# Interface.net
KiCad netlist of a schematic drawn in Altium Designer
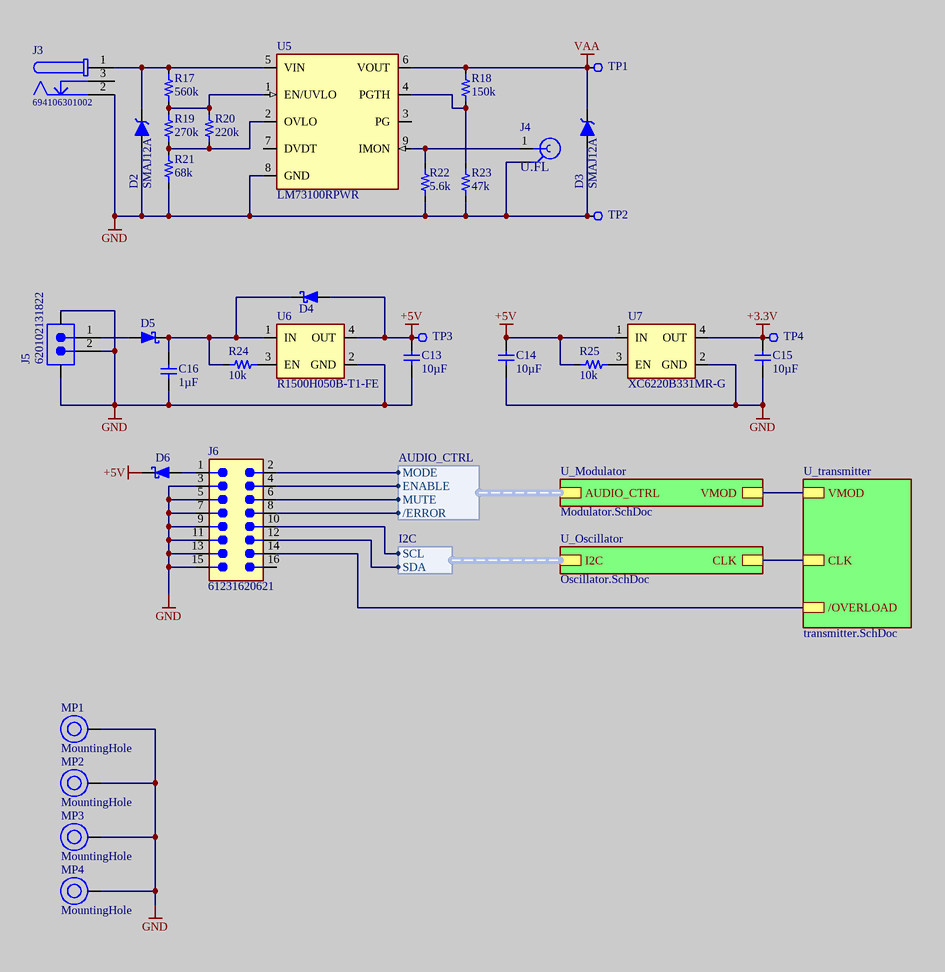
[diagram p0: Interface.SchDoc]

(export (version "E")
  (design (tool "Eeschema 10.0.6"))
  (components
    (comp (ref "C13")
      (value "10µF")
      (footprint "WCAP-CSGP_1210_L3.2W2.5H2")
      (description "WCAP-CSGP Multilayer Ceramic Chip Capacitor, General Purpose, size 1210, X7R, 10µF, 16VDC")
      (fields (field (name "TOLERANCE") "10%") (field (name "JLCPCB PART #") "C319189"))
      (libsource (lib "7c7 Engineering") (part "CAP-NP-2"))
    )
    (comp (ref "C14")
      (value "10µF")
      (footprint "WCAP-CSGP_1210_L3.2W2.5H2")
      (description "WCAP-CSGP Multilayer Ceramic Chip Capacitor, General Purpose, size 1210, X7R, 10µF, 16VDC")
      (fields (field (name "TOLERANCE") "10%") (field (name "JLCPCB PART #") "C319189"))
      (libsource (lib "7c7 Engineering") (part "CAP-NP-2"))
    )
    (comp (ref "C15")
      (value "10µF")
      (footprint "WCAP-CSGP_1210_L3.2W2.5H2")
      (description "WCAP-CSGP Multilayer Ceramic Chip Capacitor, General Purpose, size 1210, X7R, 10µF, 16VDC")
      (fields (field (name "TOLERANCE") "10%") (field (name "JLCPCB PART #") "C319189"))
      (libsource (lib "7c7 Engineering") (part "CAP-NP-2"))
    )
    (comp (ref "C16")
      (value "1µF")
      (footprint "1206-C-N")
      (description "WCAP-CSGP Multilayer Ceramic Chip Capacitor, General Purpose, size 1206, X7R, 1µF, 50VDC")
      (fields (field (name "TOLERANCE") "10%") (field (name "JLCPCB PART #") "C1848"))
      (libsource (lib "7c7 Engineering") (part "CAP-NP-2"))
    )
    (comp (ref "D2")
      (value "SMAJ12A")
      (footprint "DO-214AC_UNI")
      (description "SMAJ Series 19.9 V 0.4 kW Surface Mount Uni-Directional TVS Diode - DO-214AC")
      (fields
        (field (name "MANUFACTURER PART NUMBER") "824500121")
        (field (name "MANUFACTURER") "Wurth Elektronik")
      )
      (libsource (lib "7c7 Engineering") (part "DIODE-ZEN-2"))
    )
    (comp (ref "D3")
      (value "SMAJ12A")
      (footprint "DO-214AC_UNI")
      (description "SMAJ Series 19.9 V 0.4 kW Surface Mount Uni-Directional TVS Diode - DO-214AC")
      (fields
        (field (name "MANUFACTURER PART NUMBER") "824500121")
        (field (name "MANUFACTURER") "Wurth Elektronik")
      )
      (libsource (lib "7c7 Engineering") (part "DIODE-ZEN-2"))
    )
    (comp (ref "D4")
      (value "PMEG10020ELRX")
      (footprint "FP-SOD123W-MFG")
      (description "Diode Schottky 100V 2A 2-Pin SOD-123F T/R")
      (fields (field (name "JLCPCB PART #") "C456130") (field (name "PAGE PART #") "?"))
      (libsource (lib "7c7 Engineering") (part "DIODE-SKY-2"))
    )
    (comp (ref "D5")
      (value "PMEG10020ELRX")
      (footprint "FP-SOD123W-MFG")
      (description "Diode Schottky 100V 2A 2-Pin SOD-123F T/R")
      (fields (field (name "JLCPCB PART #") "C456130") (field (name "PAGE PART #") "?"))
      (libsource (lib "7c7 Engineering") (part "DIODE-SKY-2"))
    )
    (comp (ref "D6")
      (value "PMEG10020ELRX")
      (footprint "FP-SOD123W-MFG")
      (description "Diode Schottky 100V 2A 2-Pin SOD-123F T/R")
      (fields (field (name "JLCPCB PART #") "C456130") (field (name "PAGE PART #") "?"))
      (libsource (lib "7c7 Engineering") (part "DIODE-SKY-2"))
    )
    (comp (ref "J3")
      (value "694106301002")
      (footprint "694106301002")
      (description "WR-DC DC Power Jack Connector, Male, Right Angled, 24V, 5A")
      (fields (field (name "JLCPCB PART #") "C5184829") (field (name "MANUFACTURER") "Wurth Elektronik"))
      (libsource (lib "7c7 Engineering") (part "Symbol"))
    )
    (comp (ref "J4")
      (value "U.FL-R-SMT(10)")
      (footprint "HRS-U.FL-R-SMT_V")
      (fields (field (name "JLCPCB PART #") "C88373") (field (name "MANUFACTURER") "Hirose Electric"))
      (libsource (lib "7c7 Engineering") (part "CN_COAX"))
    )
    (comp (ref "J5")
      (value "620102131822")
      (footprint "620102131822")
      (description "WR-WTB SMT Male Horizontal Shrouded Header, pitch 2mm, 2p")
      (fields
        (field (name "JLCPCB PART #") "C295747")
        (field (name "PAGE PART #") "K620102131822")
        (field (name "PUBLISHER") "Wurth Elektronik")
      )
      (libsource (lib "7c7 Engineering") (part "HDR_2P_2MP"))
    )
    (comp (ref "J6")
      (value "61231620621")
      (footprint "61231620621")
      (description "WR-BHD Male Box Header, SMT Straight, pitch 2.54mm, 2 row, 16 pin")
      (fields (field (name "JLCPCB PART #") "C22387748") (field (name "MANUFACTURER") "Wurth Elektronik"))
      (libsource (lib "7c7 Engineering") (part "CN_M_2x8P"))
    )
    (comp (ref "MP1")
      (value "MountingHole")
      (footprint "PTH-M3D6.5_VIA-RING")
      (libsource (lib "7c7 Engineering") (part "MECH_NO_BOM"))
    )
    (comp (ref "MP2")
      (value "MountingHole")
      (footprint "PTH-M3D6.5_VIA-RING")
      (libsource (lib "7c7 Engineering") (part "MECH_NO_BOM"))
    )
    (comp (ref "MP3")
      (value "MountingHole")
      (footprint "PTH-M3D6.5_VIA-RING")
      (libsource (lib "7c7 Engineering") (part "MECH_NO_BOM"))
    )
    (comp (ref "MP4")
      (value "MountingHole")
      (footprint "PTH-M3D6.5_VIA-RING")
      (libsource (lib "7c7 Engineering") (part "MECH_NO_BOM"))
    )
    (comp (ref "R17")
      (value "560k")
      (footprint "0603-R-N")
      (description "Res Thick Film 0603 560K Ohm 1% 0.1W ±100ppm/°C Molded SMD Punched Carrier T/R")
      (fields (field (name "JLCPCB PART #") "C25822") (field (name "TOLERANCE") "1%"))
      (libsource (lib "7c7 Engineering") (part "RES"))
    )
    (comp (ref "R18")
      (value "150k")
      (footprint "0603-R-N")
      (description "Chip Resistor, Thick Film, General Purpose, 0603, 100mW, 50V, 150 kOhm, +/-1%")
      (fields (field (name "FLIR PART #") "YRES150K-1") (field (name "JLCPCB PART #") "C22807"))
      (libsource (lib "7c7 Engineering") (part "RES"))
    )
    (comp (ref "R19")
      (value "270k")
      (footprint "0603-R-N")
      (description "SMD Chip Resistor, 270 kOhm, ï¿½ 1%, 100 mW, 0603 [1608 Metric], Thick Film, General Purpose")
      (fields (field (name "JLCPCB PART #") "C22965") (field (name "TOLERANCE") "1%"))
      (libsource (lib "7c7 Engineering") (part "RES"))
    )
    (comp (ref "R20")
      (value "220k")
      (footprint "0603-R-N")
      (description "Res Thick Film 0603 220K Ohm 1% 0.1W(1/10W) ±100ppm/C Pad SMD T/R")
      (fields (field (name "TOLERANCE") "1%") (field (name "FLIR PART #") "YRES220K-1"))
      (libsource (lib "7c7 Engineering") (part "RES"))
    )
    (comp (ref "R21")
      (value "68k")
      (footprint "0603-R-N")
      (description "Chip Resistor, Thick Film, General Purpose, 0603, 100mW, 50V, 68 kOhm, +/-1%")
      (fields (field (name "TOLERANCE") "1%") (field (name "JLCPCB PART #") "C114633"))
      (libsource (lib "7c7 Engineering") (part "RES"))
    )
    (comp (ref "R22")
      (value "5.6k")
      (footprint "0603-R-N")
      (description "Res Thick Film 0603 5.6K Ohm 1% 0.1W(1/10W) ±100ppm/C Pad SMD T/R")
      (fields (field (name "JLCPCB PART #") "C23189") (field (name "TOLERANCE") "1%"))
      (libsource (lib "7c7 Engineering") (part "RES"))
    )
    (comp (ref "R23")
      (value "47k")
      (footprint "0603-R-N")
      (description "Chip Resistor, Thick Film, General Purpose, 0603, 100mW, 50V, 47 kOhm, +/-1%")
      (fields (field (name "JLCPCB PART #") "C25819") (field (name "TOLERANCE") "1%"))
      (libsource (lib "7c7 Engineering") (part "RES"))
    )
    (comp (ref "R24")
      (value "10k")
      (footprint "0603-R-N")
      (description "Chip Resistor, Thick Film, General Purpose, 0603, 100mW, 50V, 10 kOhm, +/-1%")
      (fields (field (name "TOLERANCE") "1%") (field (name "JLCPCB PART #") "C25804"))
      (libsource (lib "7c7 Engineering") (part "RES"))
    )
    (comp (ref "R25")
      (value "10k")
      (footprint "0603-R-N")
      (description "Chip Resistor, Thick Film, General Purpose, 0603, 100mW, 50V, 10 kOhm, +/-1%")
      (fields (field (name "TOLERANCE") "1%") (field (name "JLCPCB PART #") "C25804"))
      (libsource (lib "7c7 Engineering") (part "RES"))
    )
    (comp (ref "TP1")
      (value "Testpad with multiple sizes")
      (footprint "TP_1.5mm_0.3mmHole")
      (description "Testpad land")
      (libsource (lib "7c7 Engineering") (part "Testpad"))
    )
    (comp (ref "TP2")
      (value "Testpad with multiple sizes")
      (footprint "TP_1.5mm_0.3mmHole")
      (description "Testpad land")
      (libsource (lib "7c7 Engineering") (part "Testpad"))
    )
    (comp (ref "TP3")
      (value "Testpad with multiple sizes")
      (footprint "TP_1.5mm_0.3mmHole")
      (description "Testpad land")
      (libsource (lib "7c7 Engineering") (part "Testpad"))
    )
    (comp (ref "TP4")
      (value "Testpad with multiple sizes")
      (footprint "TP_1.5mm_0.3mmHole")
      (description "Testpad land")
      (libsource (lib "7c7 Engineering") (part "Testpad"))
    )
    (comp (ref "U5")
      (value "LM73100RPWR")
      (footprint "VQFN-HR")
      (description "2.7V~23V 5.5A VQFN-10-HR(2x2) Power Distribution Switches ROHS")
      (fields (field (name "JLCPCB PART #") "C3210761"))
      (libsource (lib "7c7 Engineering") (part "IC_LM73100"))
    )
    (comp (ref "U6")
      (value "R1500H050B-T1-FE")
      (footprint "SOT-89-MT5_N")
      (description "Fixed LDO 5V, 2%, 500mA, Iq 130uA, -40°C to 105*C")
      (fields (field (name "JLCPCB PART #") "C3751570"))
      (libsource (lib "7c7 Engineering") (part "LDO-with-enable"))
    )
    (comp (ref "U7")
      (value "XC6220B331MR-G")
      (footprint "SOT25-N")
      (description "Fixed LDO 3.3V, 1%, 1A, Iq 108uA, -40°C to 85°C")
      (fields (field (name "JLCPCB PART #") "C86534"))
      (libsource (lib "7c7 Engineering") (part "LDO-with-enable"))
    )
  )
  (nets
    (net (code "3") (name "+3.3V") (class "Default")
      (node (ref "C15") (pin "2") (pinfunction "2_2") (pintype "passive"))
      (node (ref "TP4") (pin "1") (pinfunction "Pad_1") (pintype "passive"))
      (node (ref "U7") (pin "4") (pinfunction "OUT_4") (pintype "power_in"))
    )
    (net (code "4") (name "+5V") (class "Default")
      (node (ref "C13") (pin "2") (pinfunction "2_2") (pintype "passive"))
      (node (ref "C14") (pin "2") (pinfunction "2_2") (pintype "passive"))
      (node (ref "D4") (pin "2") (pinfunction "A_2") (pintype "passive"))
      (node (ref "D6") (pin "1") (pinfunction "K_1") (pintype "passive"))
      (node (ref "R25") (pin "1") (pinfunction "1_1") (pintype "passive"))
      (node (ref "TP3") (pin "1") (pinfunction "Pad_1") (pintype "passive"))
      (node (ref "U6") (pin "4") (pinfunction "OUT_4") (pintype "power_in"))
      (node (ref "U7") (pin "1") (pinfunction "IN_1") (pintype "power_in"))
    )
    (net (code "9") (name "/{slash}OVERLOAD") (class "Default")
      (node (ref "J6") (pin "14") (pinfunction "14_14") (pintype "passive"))
    )
    (net (code "10") (name "GND") (class "Default")
      (node (ref "C13") (pin "1") (pinfunction "1_1") (pintype "passive"))
      (node (ref "C14") (pin "1") (pinfunction "1_1") (pintype "passive"))
      (node (ref "C15") (pin "1") (pinfunction "1_1") (pintype "passive"))
      (node (ref "C16") (pin "1") (pinfunction "1_1") (pintype "passive"))
      (node (ref "D2") (pin "2") (pinfunction "A_2") (pintype "passive"))
      (node (ref "D3") (pin "2") (pinfunction "A_2") (pintype "passive"))
      (node (ref "J3") (pin "2") (pinfunction "2_2") (pintype "passive"))
      (node (ref "J4") (pin "2") (pinfunction "GND_2") (pintype "passive"))
      (node (ref "J5") (pin "2") (pinfunction "2_2") (pintype "passive"))
      (node (ref "J5") (pin "MP1") (pinfunction "MP1_MP1") (pintype "passive"))
      (node (ref "J5") (pin "MP2") (pinfunction "MP2_MP2") (pintype "passive"))
      (node (ref "J6") (pin "11") (pinfunction "11_11") (pintype "passive"))
      (node (ref "J6") (pin "13") (pinfunction "13_13") (pintype "passive"))
      (node (ref "J6") (pin "15") (pinfunction "15_15") (pintype "passive"))
      (node (ref "J6") (pin "3") (pinfunction "3_3") (pintype "passive"))
      (node (ref "J6") (pin "5") (pinfunction "5_5") (pintype "passive"))
      (node (ref "J6") (pin "7") (pinfunction "7_7") (pintype "passive"))
      (node (ref "J6") (pin "9") (pinfunction "9_9") (pintype "passive"))
      (node (ref "MP1") (pin "1") (pinfunction "H1_1") (pintype "passive"))
      (node (ref "MP2") (pin "1") (pinfunction "H1_1") (pintype "passive"))
      (node (ref "MP3") (pin "1") (pinfunction "H1_1") (pintype "passive"))
      (node (ref "MP4") (pin "1") (pinfunction "H1_1") (pintype "passive"))
      (node (ref "R21") (pin "1") (pinfunction "1_1") (pintype "passive"))
      (node (ref "R22") (pin "1") (pinfunction "1_1") (pintype "passive"))
      (node (ref "R23") (pin "1") (pinfunction "1_1") (pintype "passive"))
      (node (ref "TP2") (pin "1") (pinfunction "Pad_1") (pintype "passive"))
      (node (ref "U5") (pin "8") (pinfunction "GND_8") (pintype "power_in"))
      (node (ref "U6") (pin "2") (pinfunction "GND_2") (pintype "power_in"))
      (node (ref "U7") (pin "2") (pinfunction "GND_2") (pintype "power_in"))
    )
    (net (code "11") (name "Net-(D2-K)") (class "Default")
      (node (ref "D2") (pin "1") (pinfunction "K_1") (pintype "passive"))
      (node (ref "J3") (pin "1") (pinfunction "1_1") (pintype "passive"))
      (node (ref "R17") (pin "2") (pinfunction "2_2") (pintype "passive"))
      (node (ref "U5") (pin "5") (pinfunction "VIN_5") (pintype "power_in"))
    )
    (net (code "12") (name "Net-(D4-K)") (class "Default")
      (node (ref "C16") (pin "2") (pinfunction "2_2") (pintype "passive"))
      (node (ref "D4") (pin "1") (pinfunction "K_1") (pintype "passive"))
      (node (ref "D5") (pin "1") (pinfunction "K_1") (pintype "passive"))
      (node (ref "R24") (pin "1") (pinfunction "1_1") (pintype "passive"))
      (node (ref "U6") (pin "1") (pinfunction "IN_1") (pintype "power_in"))
    )
    (net (code "13") (name "Net-(D5-A)") (class "Default")
      (node (ref "D5") (pin "2") (pinfunction "A_2") (pintype "passive"))
      (node (ref "J5") (pin "1") (pinfunction "1_1") (pintype "passive"))
    )
    (net (code "14") (name "Net-(D6-A)") (class "Default")
      (node (ref "D6") (pin "2") (pinfunction "A_2") (pintype "passive"))
      (node (ref "J6") (pin "1") (pinfunction "1_1") (pintype "passive"))
    )
    (net (code "15") (name "Net-(J4-SIG)") (class "Default")
      (node (ref "J4") (pin "1") (pinfunction "SIG_1") (pintype "passive"))
      (node (ref "R22") (pin "2") (pinfunction "2_2") (pintype "passive"))
      (node (ref "U5") (pin "9") (pinfunction "IMON_9") (pintype "input"))
    )
    (net (code "16") (name "Net-(U5-EN{slash}UVLO)") (class "Default")
      (node (ref "R17") (pin "1") (pinfunction "1_1") (pintype "passive"))
      (node (ref "R19") (pin "2") (pinfunction "2_2") (pintype "passive"))
      (node (ref "R20") (pin "2") (pinfunction "2_2") (pintype "passive"))
      (node (ref "U5") (pin "1") (pinfunction "EN/UVLO_1") (pintype "input"))
    )
    (net (code "17") (name "Net-(U5-OVLO)") (class "Default")
      (node (ref "R19") (pin "1") (pinfunction "1_1") (pintype "passive"))
      (node (ref "R20") (pin "1") (pinfunction "1_1") (pintype "passive"))
      (node (ref "R21") (pin "2") (pinfunction "2_2") (pintype "passive"))
      (node (ref "U5") (pin "2") (pinfunction "OVLO_2") (pintype "passive"))
    )
    (net (code "18") (name "Net-(U5-PGTH)") (class "Default")
      (node (ref "R18") (pin "2") (pinfunction "2_2") (pintype "passive"))
      (node (ref "R23") (pin "2") (pinfunction "2_2") (pintype "passive"))
      (node (ref "U5") (pin "4") (pinfunction "PGTH_4") (pintype "passive"))
    )
    (net (code "19") (name "Net-(U6-EN)") (class "Default")
      (node (ref "R24") (pin "2") (pinfunction "2_2") (pintype "passive"))
      (node (ref "U6") (pin "3") (pinfunction "EN_3") (pintype "passive"))
    )
    (net (code "20") (name "Net-(U7-EN)") (class "Default")
      (node (ref "R25") (pin "2") (pinfunction "2_2") (pintype "passive"))
      (node (ref "U7") (pin "3") (pinfunction "EN_3") (pintype "passive"))
    )
    (net (code "21") (name "VAA") (class "Default")
      (node (ref "D3") (pin "1") (pinfunction "K_1") (pintype "passive"))
      (node (ref "R18") (pin "1") (pinfunction "1_1") (pintype "passive"))
      (node (ref "TP1") (pin "1") (pinfunction "Pad_1") (pintype "passive"))
      (node (ref "U5") (pin "6") (pinfunction "VOUT_6") (pintype "passive"))
    )
    (net (code "22") (name "unconnected-(J3-Pad3)") (class "Default")
      (node (ref "J3") (pin "3") (pinfunction "3_3") (pintype "passive"))
    )
    (net (code "23") (name "unconnected-(J6-Pad2)") (class "Default")
      (node (ref "J6") (pin "2") (pinfunction "2_2") (pintype "passive"))
    )
    (net (code "24") (name "unconnected-(J6-Pad4)") (class "Default")
      (node (ref "J6") (pin "4") (pinfunction "4_4") (pintype "passive"))
    )
    (net (code "25") (name "unconnected-(J6-Pad6)") (class "Default")
      (node (ref "J6") (pin "6") (pinfunction "6_6") (pintype "passive"))
    )
    (net (code "26") (name "unconnected-(J6-Pad8)") (class "Default")
      (node (ref "J6") (pin "8") (pinfunction "8_8") (pintype "passive"))
    )
    (net (code "27") (name "unconnected-(J6-Pad10)") (class "Default")
      (node (ref "J6") (pin "10") (pinfunction "10_10") (pintype "passive"))
    )
    (net (code "28") (name "unconnected-(J6-Pad12)") (class "Default")
      (node (ref "J6") (pin "12") (pinfunction "12_12") (pintype "passive"))
    )
    (net (code "29") (name "unconnected-(J6-Pad16)") (class "Default")
      (node (ref "J6") (pin "16") (pinfunction "16_16") (pintype "passive"))
    )
    (net (code "30") (name "unconnected-(U5-DVDT-Pad7)") (class "Default")
      (node (ref "U5") (pin "7") (pinfunction "DVDT_7") (pintype "passive"))
    )
    (net (code "31") (name "unconnected-(U5-PG-Pad3)") (class "Default")
      (node (ref "U5") (pin "3") (pinfunction "PG_3") (pintype "open_collector"))
    )
  )
)
